# version_2.net
KiCad netlist of a schematic drawn in EAGLE
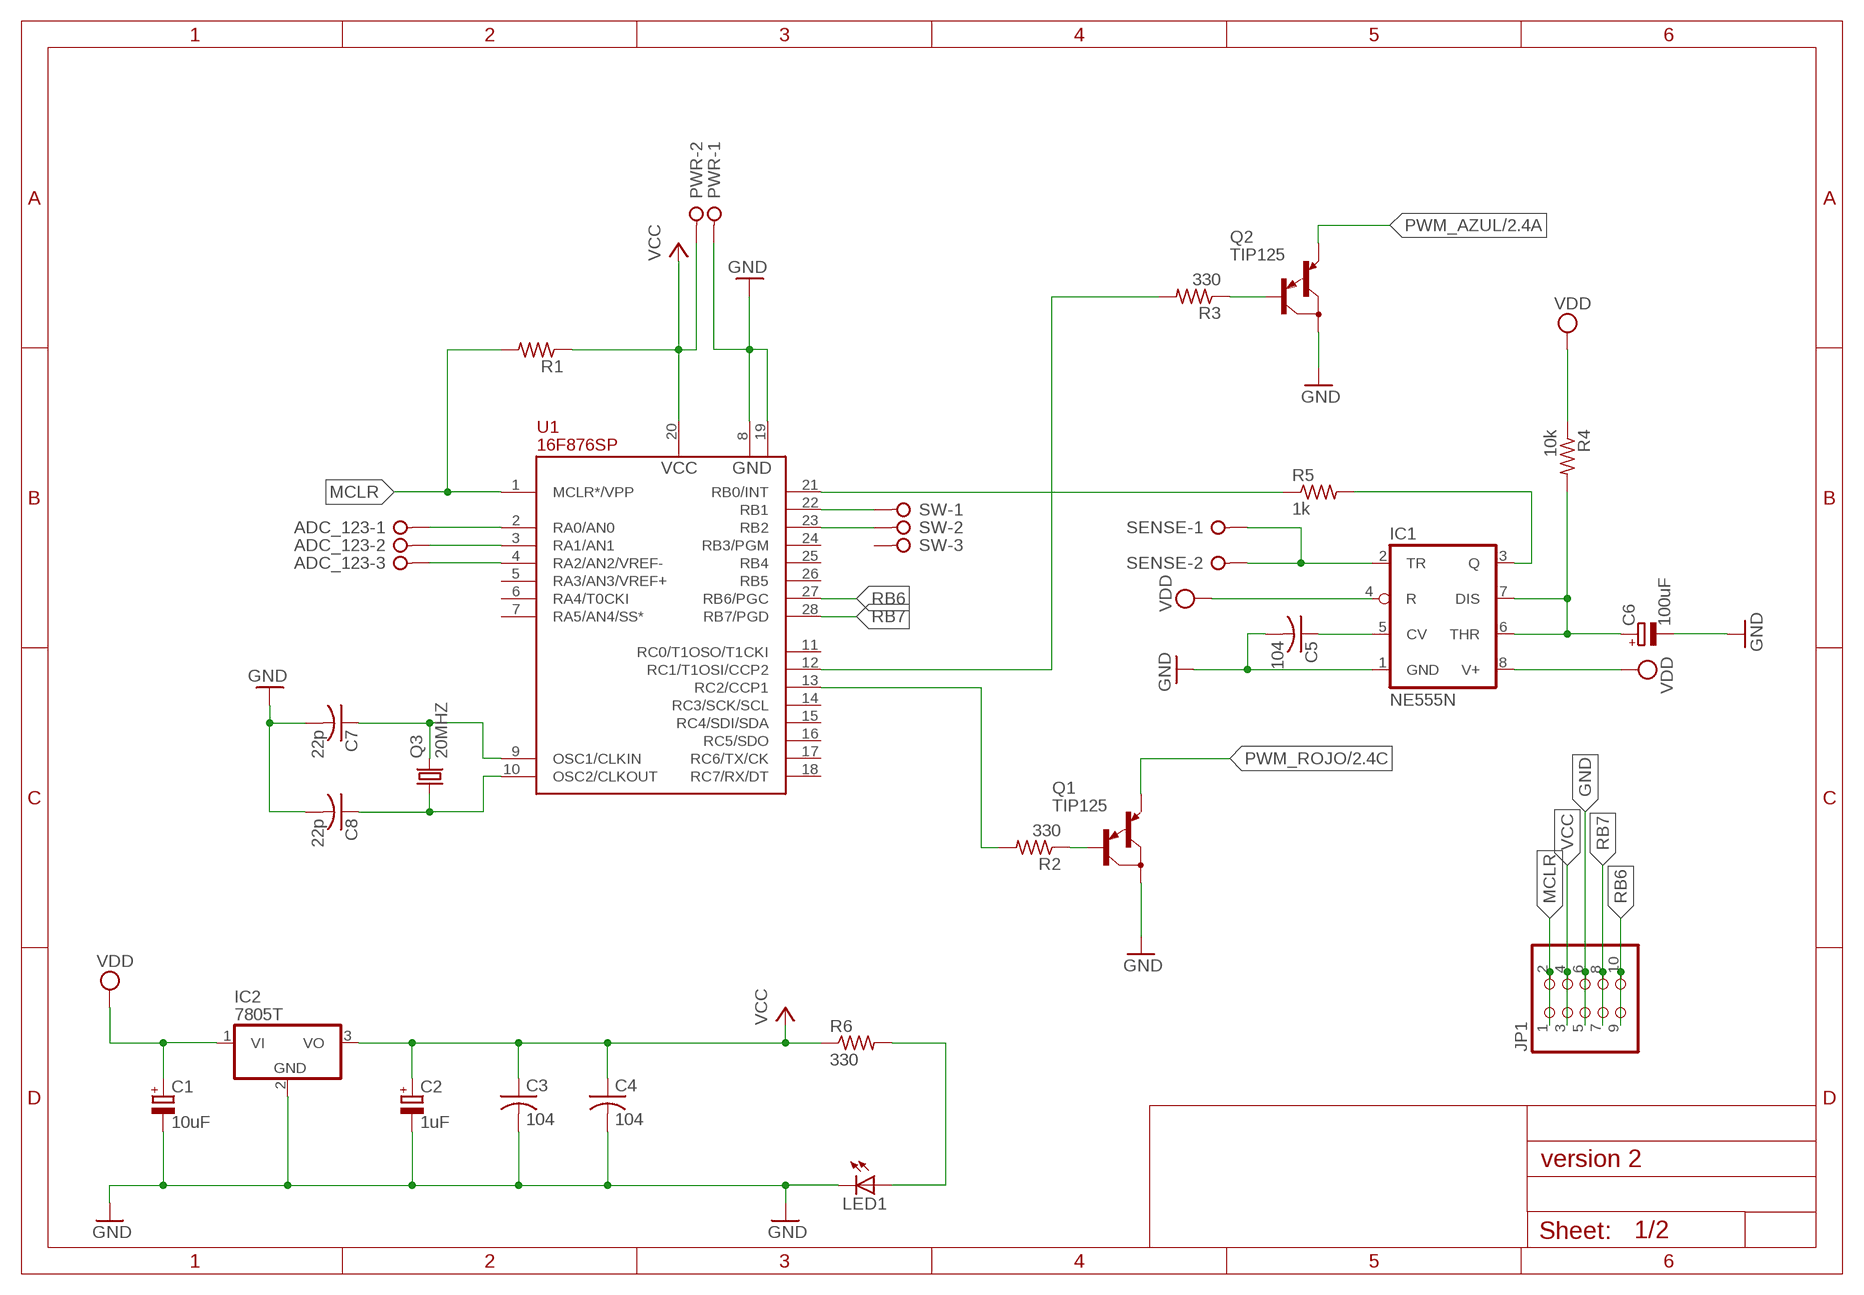
[diagram p0: schematic, sheet 1]
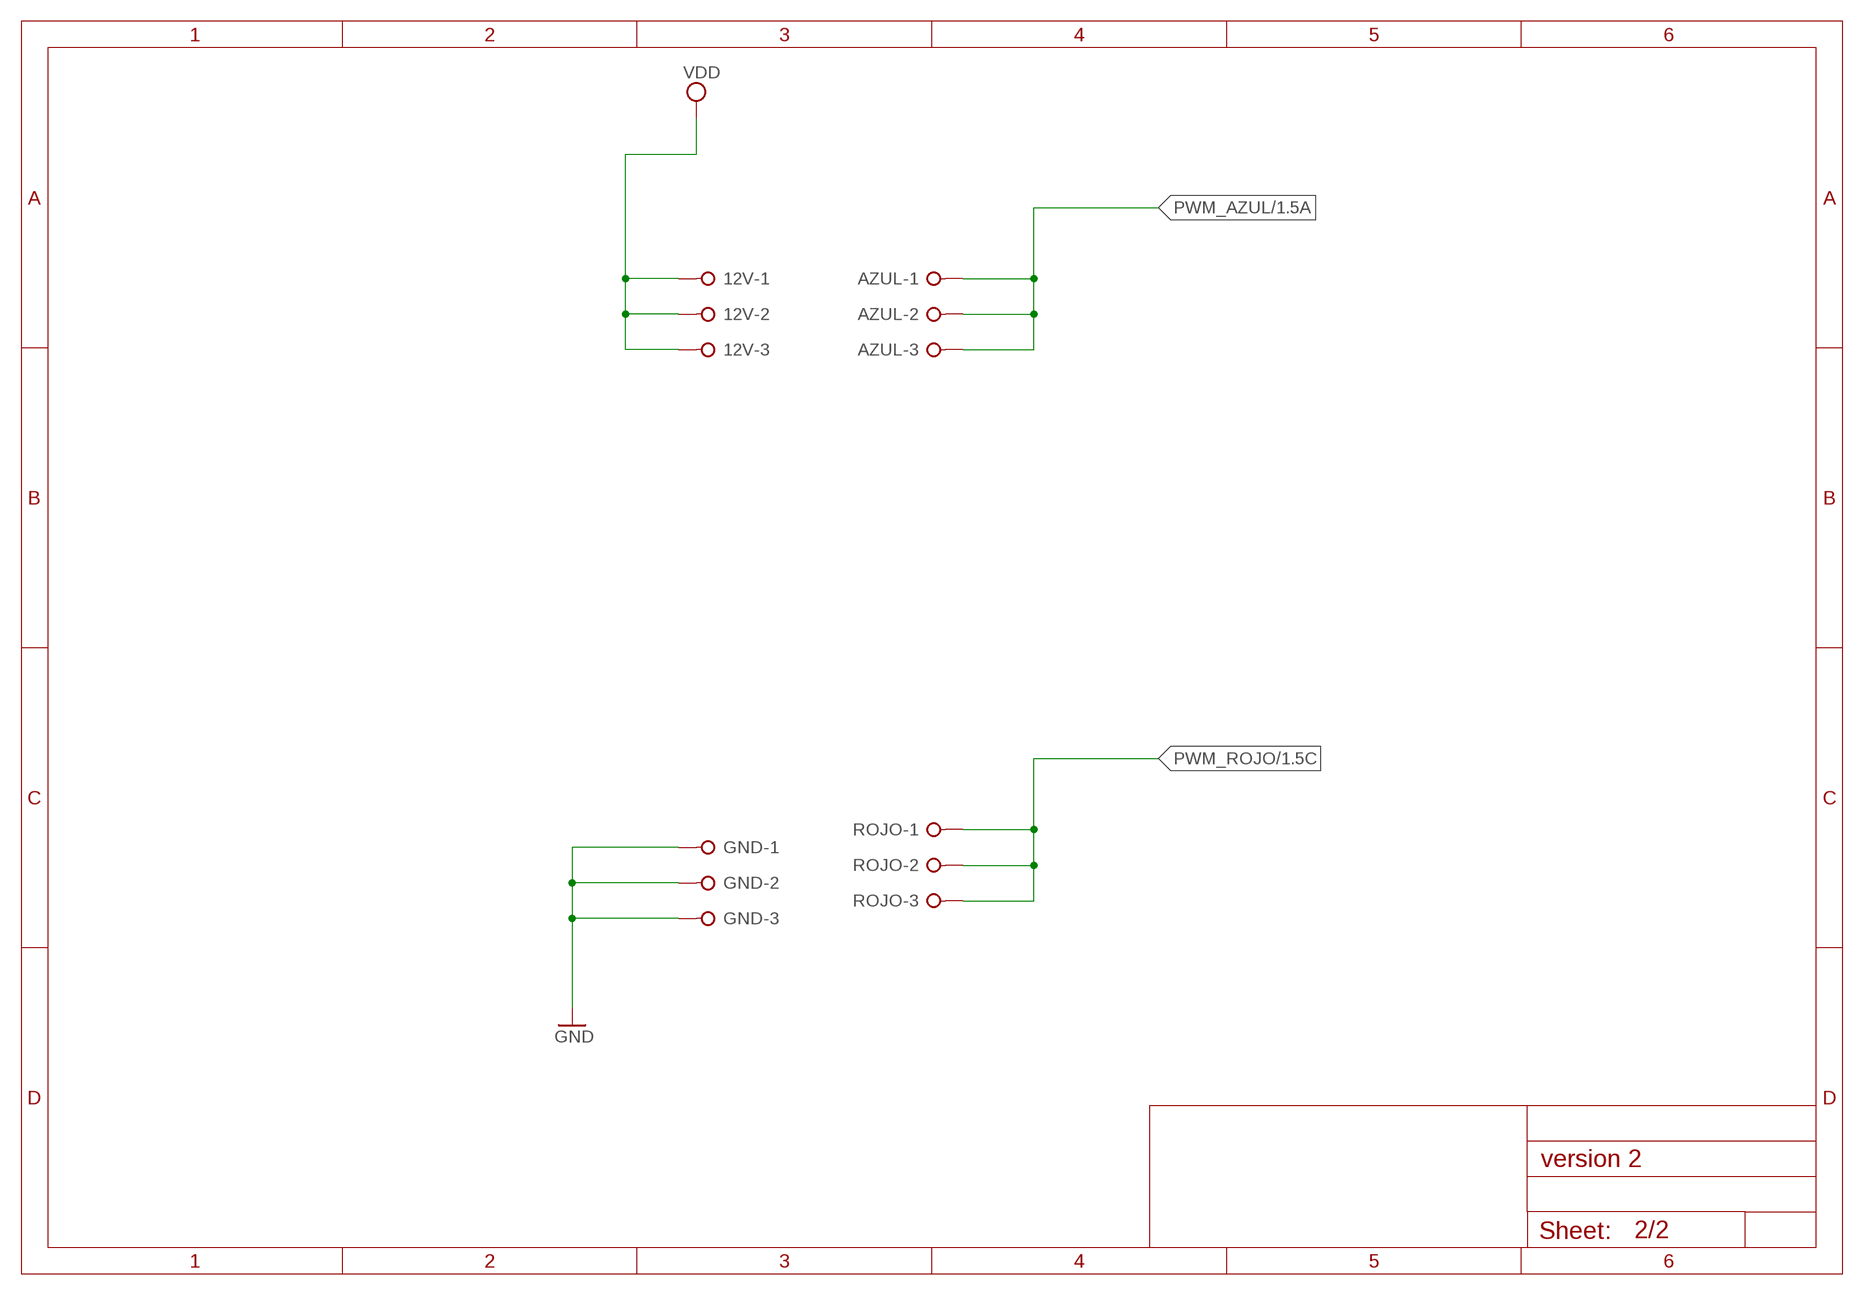
[diagram p1: schematic, sheet 2]

(export (version "E")
  (design (tool "Eeschema 10.0.6"))
  (components
    (comp (ref "ADC_123")
      (value "W237-03P")
      (footprint "eagle-import:W237-133")
      (libsource (lib "eagle-import") (part "W237-03P"))
    )
    (comp (ref "C1")
      (value "10uF")
      (footprint "eagle-import:E2,5-6")
      (libsource (lib "eagle-import") (part "CPOL-EUE2.5-6"))
    )
    (comp (ref "C2")
      (value "1uF")
      (footprint "eagle-import:E2,5-6")
      (libsource (lib "eagle-import") (part "CPOL-EUE2.5-6"))
    )
    (comp (ref "C3")
      (value "104")
      (footprint "eagle-import:C025-024X044")
      (libsource (lib "eagle-import") (part "C-US025-024X044"))
    )
    (comp (ref "C4")
      (value "104")
      (footprint "eagle-import:C025-024X044")
      (libsource (lib "eagle-import") (part "C-US025-024X044"))
    )
    (comp (ref "C5")
      (value "104")
      (footprint "eagle-import:C025-024X044")
      (libsource (lib "eagle-import") (part "C-US025-024X044"))
    )
    (comp (ref "C6")
      (value "100uF")
      (footprint "eagle-import:E2,5-6")
      (libsource (lib "eagle-import") (part "CPOL-EUE2.5-6"))
    )
    (comp (ref "C7")
      (value "22p")
      (footprint "eagle-import:C025-024X044")
      (libsource (lib "eagle-import") (part "C-US025-024X044"))
    )
    (comp (ref "C8")
      (value "22p")
      (footprint "eagle-import:C025-024X044")
      (libsource (lib "eagle-import") (part "C-US025-024X044"))
    )
    (comp (ref "IC1")
      (value "NE555N")
      (footprint "eagle-import:DIL08")
      (libsource (lib "eagle-import") (part "555NNE"))
    )
    (comp (ref "IC2")
      (value "7805T")
      (footprint "eagle-import:TO220H")
      (libsource (lib "eagle-import") (part "78T05"))
    )
    (comp (ref "JP1")
      (value "PINHD-2X5")
      (footprint "eagle-import:2X05")
      (libsource (lib "eagle-import") (part "PINHD-2X5"))
    )
    (comp (ref "LED1")
      (value "LED3MM")
      (footprint "eagle-import:LED3MM")
      (libsource (lib "eagle-import") (part "LED3MM"))
    )
    (comp (ref "PWR")
      (value "W237-02P")
      (footprint "eagle-import:W237-132")
      (libsource (lib "eagle-import") (part "W237-02P"))
    )
    (comp (ref "Q1")
      (value "TIP125")
      (footprint "eagle-import:TO220")
      (libsource (lib "eagle-import") (part "TIP125"))
    )
    (comp (ref "Q2")
      (value "TIP125")
      (footprint "eagle-import:TO220")
      (libsource (lib "eagle-import") (part "TIP125"))
    )
    (comp (ref "Q3")
      (value "20MHZ")
      (footprint "eagle-import:HC49_S")
      (libsource (lib "eagle-import") (part "CRYSTALHC49S"))
    )
    (comp (ref "R1")
      (value "R-US_0204/7")
      (footprint "eagle-import:0204_7")
      (libsource (lib "eagle-import") (part "R-US_0204/7"))
    )
    (comp (ref "R2")
      (value "330")
      (footprint "eagle-import:0204_7")
      (libsource (lib "eagle-import") (part "R-US_0204/7"))
    )
    (comp (ref "R3")
      (value "330")
      (footprint "eagle-import:0204_7")
      (libsource (lib "eagle-import") (part "R-US_0204/7"))
    )
    (comp (ref "R4")
      (value "10k")
      (footprint "eagle-import:0204_7")
      (libsource (lib "eagle-import") (part "R-US_0204/7"))
    )
    (comp (ref "R5")
      (value "1k")
      (footprint "eagle-import:0204_7")
      (libsource (lib "eagle-import") (part "R-US_0204/7"))
    )
    (comp (ref "R6")
      (value "330")
      (footprint "eagle-import:0204_7")
      (libsource (lib "eagle-import") (part "R-US_0204/7"))
    )
    (comp (ref "SENSE")
      (value "W237-02P")
      (footprint "eagle-import:W237-132")
      (libsource (lib "eagle-import") (part "W237-02P"))
    )
    (comp (ref "SW")
      (value "W237-03P")
      (footprint "eagle-import:W237-133")
      (libsource (lib "eagle-import") (part "W237-03P"))
    )
    (comp (ref "U1")
      (value "16F876SP")
      (footprint "eagle-import:DIL28-3")
      (libsource (lib "eagle-import") (part "16F876SP"))
    )
    (comp (ref "12V")
      (value "W237-03P")
      (footprint "eagle-import:W237-133")
      (libsource (lib "eagle-import") (part "W237-03P"))
    )
    (comp (ref "AZUL")
      (value "W237-03P")
      (footprint "eagle-import:W237-133")
      (libsource (lib "eagle-import") (part "W237-03P"))
    )
    (comp (ref "GND")
      (value "W237-03P")
      (footprint "eagle-import:W237-133")
      (libsource (lib "eagle-import") (part "W237-03P"))
    )
    (comp (ref "ROJO")
      (value "W237-03P")
      (footprint "eagle-import:W237-133")
      (libsource (lib "eagle-import") (part "W237-03P"))
    )
  )
  (nets
    (net (code "1") (name "GND") (class "Default")
      (node (ref "C1") (pin "-") (pinfunction "-_-") (pintype "passive"))
      (node (ref "C2") (pin "-") (pinfunction "-_-") (pintype "passive"))
      (node (ref "C3") (pin "2") (pinfunction "2_2") (pintype "passive"))
      (node (ref "C4") (pin "2") (pinfunction "2_2") (pintype "passive"))
      (node (ref "C5") (pin "2") (pinfunction "2_2") (pintype "passive"))
      (node (ref "C6") (pin "-") (pinfunction "-_-") (pintype "passive"))
      (node (ref "C7") (pin "2") (pinfunction "2_2") (pintype "passive"))
      (node (ref "C8") (pin "2") (pinfunction "2_2") (pintype "passive"))
      (node (ref "GND") (pin "1") (pinfunction "KL_1") (pintype "passive"))
      (node (ref "GND") (pin "2") (pinfunction "KL_2") (pintype "passive"))
      (node (ref "GND") (pin "3") (pinfunction "KL_3") (pintype "passive"))
      (node (ref "IC1") (pin "1") (pinfunction "GND_1") (pintype "power_in"))
      (node (ref "IC2") (pin "2") (pinfunction "GND_2") (pintype "passive"))
      (node (ref "JP1") (pin "5") (pinfunction "5_5") (pintype "passive"))
      (node (ref "JP1") (pin "6") (pinfunction "6_6") (pintype "passive"))
      (node (ref "LED1") (pin "K") (pinfunction "C_K") (pintype "passive"))
      (node (ref "PWR") (pin "1") (pinfunction "KL_1") (pintype "passive"))
      (node (ref "Q1") (pin "2") (pinfunction "C_2") (pintype "passive"))
      (node (ref "Q2") (pin "2") (pinfunction "C_2") (pintype "passive"))
      (node (ref "U1") (pin "19") (pinfunction "GND_19") (pintype "power_in"))
      (node (ref "U1") (pin "8") (pinfunction "GND_8") (pintype "power_in"))
    )
    (net (code "2") (name "MCLR") (class "Default")
      (node (ref "JP1") (pin "1") (pinfunction "1_1") (pintype "passive"))
      (node (ref "JP1") (pin "2") (pinfunction "2_2") (pintype "passive"))
      (node (ref "R1") (pin "2") (pinfunction "2_2") (pintype "passive"))
      (node (ref "U1") (pin "1") (pinfunction "MCLR*/VPP_1") (pintype "bidirectional"))
    )
    (net (code "3") (name "Net-(ADC_123A-KL)") (class "Default")
      (node (ref "ADC_123") (pin "1") (pinfunction "KL_1") (pintype "passive"))
      (node (ref "U1") (pin "2") (pinfunction "RA0/AN0_2") (pintype "bidirectional"))
    )
    (net (code "4") (name "Net-(ADC_123B-KL)") (class "Default")
      (node (ref "ADC_123") (pin "2") (pinfunction "KL_2") (pintype "passive"))
      (node (ref "U1") (pin "3") (pinfunction "RA1/AN1_3") (pintype "bidirectional"))
    )
    (net (code "5") (name "Net-(ADC_123C-KL)") (class "Default")
      (node (ref "ADC_123") (pin "3") (pinfunction "KL_3") (pintype "passive"))
      (node (ref "U1") (pin "4") (pinfunction "RA2/AN2/VREF-_4") (pintype "bidirectional"))
    )
    (net (code "6") (name "Net-(IC1-CV)") (class "Default")
      (node (ref "C5") (pin "1") (pinfunction "1_1") (pintype "passive"))
      (node (ref "IC1") (pin "5") (pinfunction "CV_5") (pintype "input"))
    )
    (net (code "7") (name "Net-(IC1-DIS)") (class "Default")
      (node (ref "C6") (pin "+") (pinfunction "+_+") (pintype "passive"))
      (node (ref "IC1") (pin "6") (pinfunction "THR_6") (pintype "input"))
      (node (ref "IC1") (pin "7") (pinfunction "DIS_7") (pintype "input"))
      (node (ref "R4") (pin "2") (pinfunction "2_2") (pintype "passive"))
    )
    (net (code "8") (name "Net-(IC1-Q)") (class "Default")
      (node (ref "IC1") (pin "3") (pinfunction "Q_3") (pintype "output"))
      (node (ref "R5") (pin "2") (pinfunction "2_2") (pintype "passive"))
    )
    (net (code "9") (name "Net-(IC1-TR)") (class "Default")
      (node (ref "IC1") (pin "2") (pinfunction "TR_2") (pintype "input"))
      (node (ref "SENSE") (pin "1") (pinfunction "KL_1") (pintype "passive"))
      (node (ref "SENSE") (pin "2") (pinfunction "KL_2") (pintype "passive"))
    )
    (net (code "10") (name "Net-(LED1-PadA)") (class "Default")
      (node (ref "LED1") (pin "A") (pinfunction "A_A") (pintype "passive"))
      (node (ref "R6") (pin "2") (pinfunction "2_2") (pintype "passive"))
    )
    (net (code "11") (name "Net-(Q1-B)") (class "Default")
      (node (ref "Q1") (pin "1") (pinfunction "B_1") (pintype "passive"))
      (node (ref "R2") (pin "1") (pinfunction "1_1") (pintype "passive"))
    )
    (net (code "12") (name "Net-(Q2-B)") (class "Default")
      (node (ref "Q2") (pin "1") (pinfunction "B_1") (pintype "passive"))
      (node (ref "R3") (pin "1") (pinfunction "1_1") (pintype "passive"))
    )
    (net (code "13") (name "Net-(SWA-KL)") (class "Default")
      (node (ref "SW") (pin "1") (pinfunction "KL_1") (pintype "passive"))
      (node (ref "U1") (pin "22") (pinfunction "RB1_22") (pintype "bidirectional"))
    )
    (net (code "14") (name "Net-(SWB-KL)") (class "Default")
      (node (ref "SW") (pin "2") (pinfunction "KL_2") (pintype "passive"))
      (node (ref "U1") (pin "23") (pinfunction "RB2_23") (pintype "bidirectional"))
    )
    (net (code "15") (name "Net-(U1-OSC1{slash}CLKIN)") (class "Default")
      (node (ref "C7") (pin "1") (pinfunction "1_1") (pintype "passive"))
      (node (ref "Q3") (pin "2") (pinfunction "2_2") (pintype "passive"))
      (node (ref "U1") (pin "9") (pinfunction "OSC1/CLKIN_9") (pintype "bidirectional"))
    )
    (net (code "16") (name "Net-(U1-OSC2{slash}CLKOUT)") (class "Default")
      (node (ref "C8") (pin "1") (pinfunction "1_1") (pintype "passive"))
      (node (ref "Q3") (pin "1") (pinfunction "1_1") (pintype "passive"))
      (node (ref "U1") (pin "10") (pinfunction "OSC2/CLKOUT_10") (pintype "bidirectional"))
    )
    (net (code "17") (name "Net-(U1-RB0{slash}INT)") (class "Default")
      (node (ref "R5") (pin "1") (pinfunction "1_1") (pintype "passive"))
      (node (ref "U1") (pin "21") (pinfunction "RB0/INT_21") (pintype "bidirectional"))
    )
    (net (code "18") (name "Net-(U1-RC1{slash}T1OSI{slash}CCP2)") (class "Default")
      (node (ref "R3") (pin "2") (pinfunction "2_2") (pintype "passive"))
      (node (ref "U1") (pin "12") (pinfunction "RC1/T1OSI/CCP2_12") (pintype "bidirectional"))
    )
    (net (code "19") (name "Net-(U1-RC2{slash}CCP1)") (class "Default")
      (node (ref "R2") (pin "2") (pinfunction "2_2") (pintype "passive"))
      (node (ref "U1") (pin "13") (pinfunction "RC2/CCP1_13") (pintype "bidirectional"))
    )
    (net (code "20") (name "PWM_AZUL") (class "Default")
      (node (ref "AZUL") (pin "1") (pinfunction "KL_1") (pintype "passive"))
      (node (ref "AZUL") (pin "2") (pinfunction "KL_2") (pintype "passive"))
      (node (ref "AZUL") (pin "3") (pinfunction "KL_3") (pintype "passive"))
      (node (ref "Q2") (pin "3") (pinfunction "E_3") (pintype "passive"))
    )
    (net (code "21") (name "PWM_ROJO") (class "Default")
      (node (ref "Q1") (pin "3") (pinfunction "E_3") (pintype "passive"))
      (node (ref "ROJO") (pin "1") (pinfunction "KL_1") (pintype "passive"))
      (node (ref "ROJO") (pin "2") (pinfunction "KL_2") (pintype "passive"))
      (node (ref "ROJO") (pin "3") (pinfunction "KL_3") (pintype "passive"))
    )
    (net (code "22") (name "RB6") (class "Default")
      (node (ref "JP1") (pin "10") (pinfunction "10_10") (pintype "passive"))
      (node (ref "JP1") (pin "9") (pinfunction "9_9") (pintype "passive"))
      (node (ref "U1") (pin "27") (pinfunction "RB6/PGC_27") (pintype "bidirectional"))
    )
    (net (code "23") (name "RB7") (class "Default")
      (node (ref "JP1") (pin "7") (pinfunction "7_7") (pintype "passive"))
      (node (ref "JP1") (pin "8") (pinfunction "8_8") (pintype "passive"))
      (node (ref "U1") (pin "28") (pinfunction "RB7/PGD_28") (pintype "bidirectional"))
    )
    (net (code "24") (name "VCC") (class "Default")
      (node (ref "C2") (pin "+") (pinfunction "+_+") (pintype "passive"))
      (node (ref "C3") (pin "1") (pinfunction "1_1") (pintype "passive"))
      (node (ref "C4") (pin "1") (pinfunction "1_1") (pintype "passive"))
      (node (ref "IC2") (pin "3") (pinfunction "VO_3") (pintype "passive"))
      (node (ref "JP1") (pin "3") (pinfunction "3_3") (pintype "passive"))
      (node (ref "JP1") (pin "4") (pinfunction "4_4") (pintype "passive"))
      (node (ref "PWR") (pin "2") (pinfunction "KL_2") (pintype "passive"))
      (node (ref "R1") (pin "1") (pinfunction "1_1") (pintype "passive"))
      (node (ref "R6") (pin "1") (pinfunction "1_1") (pintype "passive"))
      (node (ref "U1") (pin "20") (pinfunction "VCC_20") (pintype "power_in"))
    )
    (net (code "25") (name "VDD") (class "Default")
      (node (ref "12V") (pin "1") (pinfunction "KL_1") (pintype "passive"))
      (node (ref "12V") (pin "2") (pinfunction "KL_2") (pintype "passive"))
      (node (ref "12V") (pin "3") (pinfunction "KL_3") (pintype "passive"))
      (node (ref "C1") (pin "+") (pinfunction "+_+") (pintype "passive"))
      (node (ref "IC1") (pin "4") (pinfunction "R_4") (pintype "input"))
      (node (ref "IC1") (pin "8") (pinfunction "V+_8") (pintype "power_in"))
      (node (ref "IC2") (pin "1") (pinfunction "VI_1") (pintype "input"))
      (node (ref "R4") (pin "1") (pinfunction "1_1") (pintype "passive"))
    )
    (net (code "26") (name "unconnected-(SWC-KL-Pad3)") (class "Default")
      (node (ref "SW") (pin "3") (pinfunction "KL_3") (pintype "passive"))
    )
    (net (code "27") (name "unconnected-(U1-RA3{slash}AN3{slash}VREF+-Pad5)") (class "Default")
      (node (ref "U1") (pin "5") (pinfunction "RA3/AN3/VREF+_5") (pintype "bidirectional"))
    )
    (net (code "28") (name "unconnected-(U1-RA4{slash}T0CKI-Pad6)") (class "Default")
      (node (ref "U1") (pin "6") (pinfunction "RA4/T0CKI_6") (pintype "bidirectional"))
    )
    (net (code "29") (name "unconnected-(U1-RA5{slash}AN4{slash}SS*-Pad7)") (class "Default")
      (node (ref "U1") (pin "7") (pinfunction "RA5/AN4/SS*_7") (pintype "bidirectional"))
    )
    (net (code "30") (name "unconnected-(U1-RB3{slash}PGM-Pad24)") (class "Default")
      (node (ref "U1") (pin "24") (pinfunction "RB3/PGM_24") (pintype "bidirectional"))
    )
    (net (code "31") (name "unconnected-(U1-RB4-Pad25)") (class "Default")
      (node (ref "U1") (pin "25") (pinfunction "RB4_25") (pintype "bidirectional"))
    )
    (net (code "32") (name "unconnected-(U1-RB5-Pad26)") (class "Default")
      (node (ref "U1") (pin "26") (pinfunction "RB5_26") (pintype "bidirectional"))
    )
    (net (code "33") (name "unconnected-(U1-RC0{slash}T1OSO{slash}T1CKI-Pad11)") (class "Default")
      (node (ref "U1") (pin "11") (pinfunction "RC0/T1OSO/T1CKI_11") (pintype "bidirectional"))
    )
    (net (code "34") (name "unconnected-(U1-RC3{slash}SCK{slash}SCL-Pad14)") (class "Default")
      (node (ref "U1") (pin "14") (pinfunction "RC3/SCK/SCL_14") (pintype "bidirectional"))
    )
    (net (code "35") (name "unconnected-(U1-RC4{slash}SDI{slash}SDA-Pad15)") (class "Default")
      (node (ref "U1") (pin "15") (pinfunction "RC4/SDI/SDA_15") (pintype "bidirectional"))
    )
    (net (code "36") (name "unconnected-(U1-RC5{slash}SDO-Pad16)") (class "Default")
      (node (ref "U1") (pin "16") (pinfunction "RC5/SDO_16") (pintype "bidirectional"))
    )
    (net (code "37") (name "unconnected-(U1-RC6{slash}TX{slash}CK-Pad17)") (class "Default")
      (node (ref "U1") (pin "17") (pinfunction "RC6/TX/CK_17") (pintype "bidirectional"))
    )
    (net (code "38") (name "unconnected-(U1-RC7{slash}RX{slash}DT-Pad18)") (class "Default")
      (node (ref "U1") (pin "18") (pinfunction "RC7/RX/DT_18") (pintype "bidirectional"))
    )
  )
)
